# Developer_GT06.net
KiCad netlist of a schematic drawn in Altium Designer
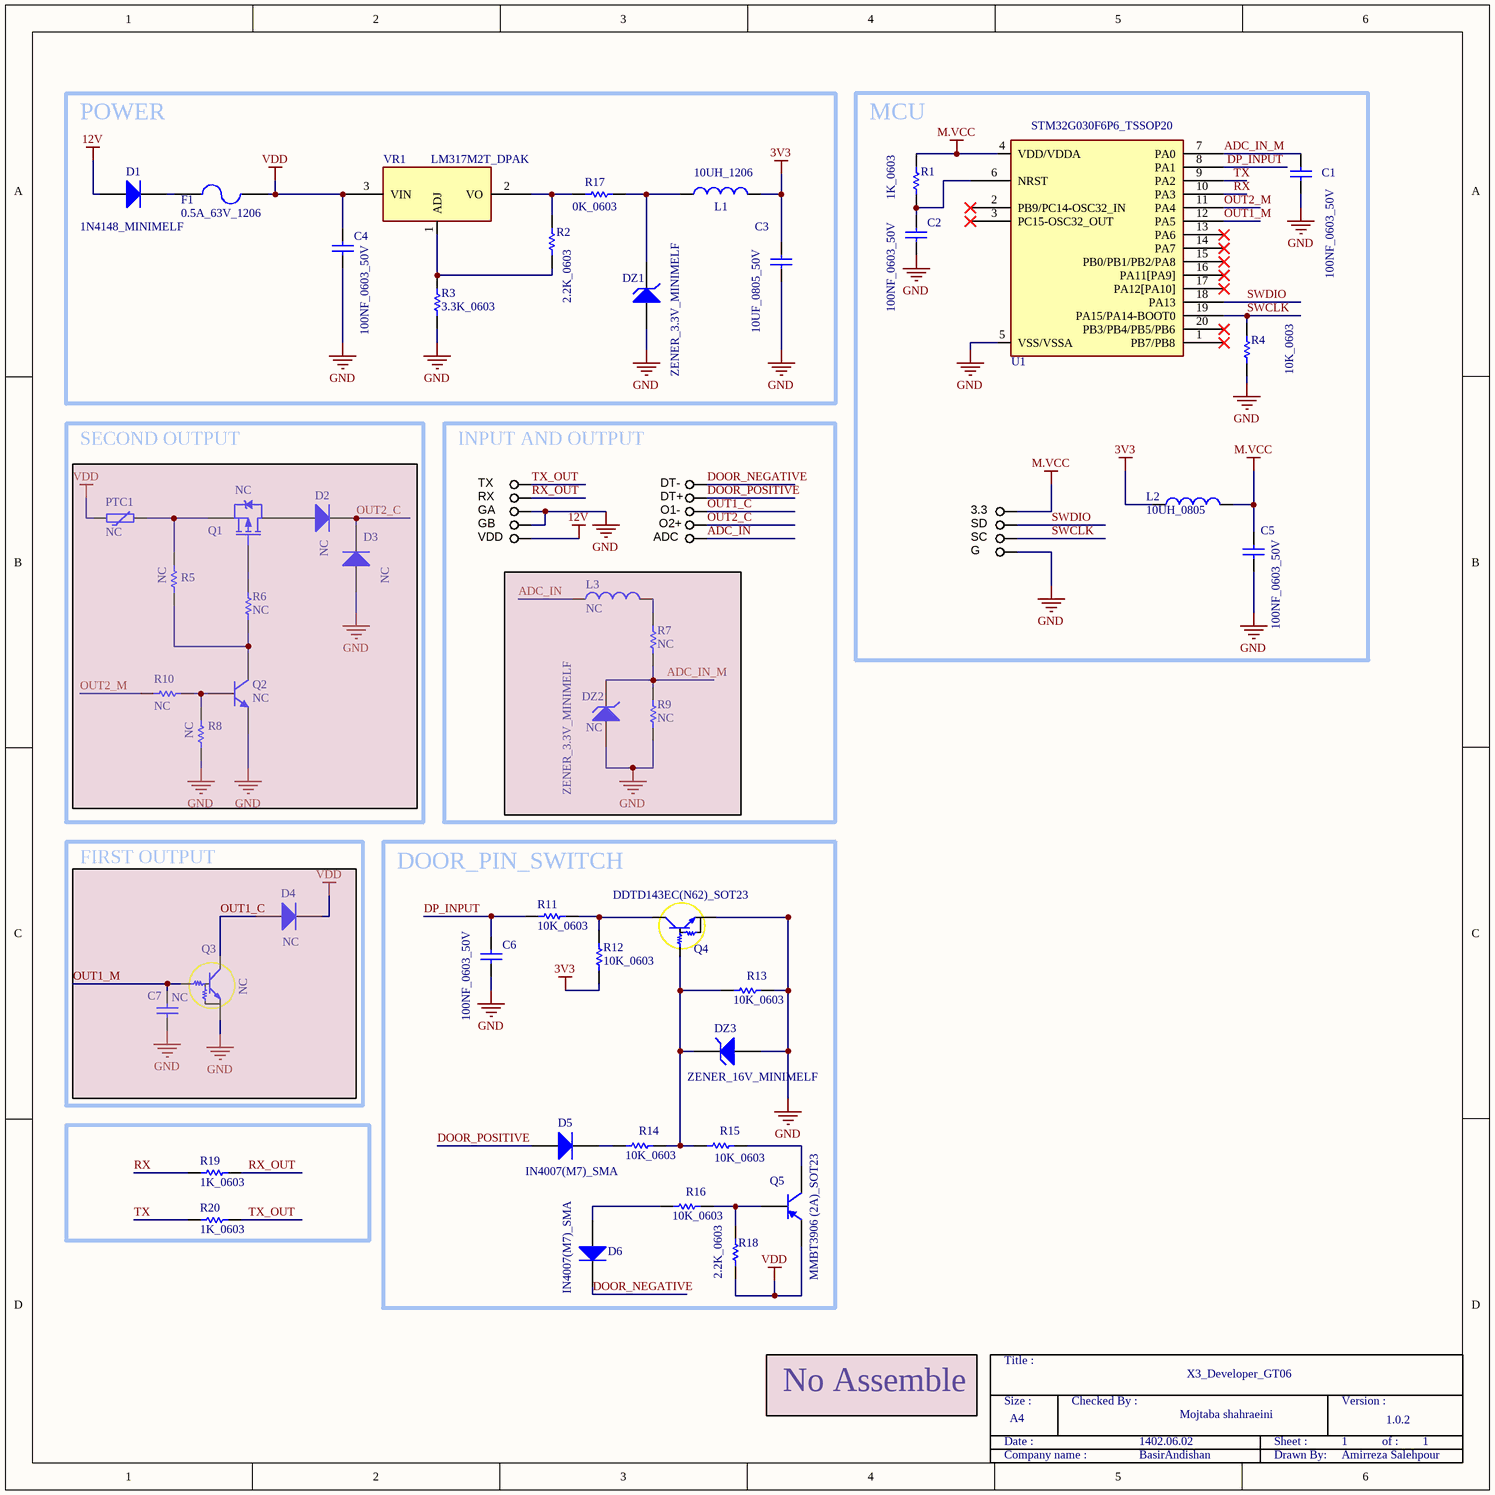
[diagram p0: Developer_GT06.SchDoc]

(export (version "E")
  (design (tool "Eeschema 10.0.6"))
  (components
    (comp (ref "3.3")
      (value "~")
      (footprint "TPSMD_D1")
      (description "TEST POINT")
      (fields (field (name "MANF") "MANF") (field (name "MANF_P#") "MANF_P#"))
      (libsource (lib "GTC Schematic") (part "TESTPOINT_SMD"))
    )
    (comp (ref "ADC")
      (value "~")
      (footprint "TPSMD_D1")
      (description "TEST POINT")
      (fields (field (name "MANF") "MANF") (field (name "MANF_P#") "MANF_P#"))
      (libsource (lib "GTC Schematic") (part "TESTPOINT_SMD"))
    )
    (comp (ref "C1")
      (value "100NF_0603_50V")
      (footprint "Cap_0603_Nominal")
      (libsource (lib "Saeed_New_Lib") (part "Cap"))
    )
    (comp (ref "C2")
      (value "100NF_0603_50V")
      (footprint "Cap_0603_Nominal")
      (libsource (lib "Saeed_New_Lib") (part "Cap"))
    )
    (comp (ref "C3")
      (value "10UF_0805_50V")
      (footprint "Cap_0805_Nominal")
      (libsource (lib "Saeed_New_Lib") (part "Cap"))
    )
    (comp (ref "C4")
      (value "100NF_0603_50V")
      (footprint "Cap_0603_Nominal")
      (libsource (lib "Saeed_New_Lib") (part "Cap"))
    )
    (comp (ref "C5")
      (value "100NF_0603_50V")
      (footprint "Cap_0603_Nominal")
      (libsource (lib "Saeed_New_Lib") (part "Cap"))
    )
    (comp (ref "C6")
      (value "100NF_0603_50V")
      (footprint "Cap_0603_Nominal")
      (libsource (lib "Saeed_New_Lib") (part "Cap"))
    )
    (comp (ref "C7")
      (value "NC")
      (footprint "Cap_0603_Nominal")
      (description "100NF_0603_50V")
      (libsource (lib "Saeed_New_Lib") (part "Cap"))
    )
    (comp (ref "D1")
      (value "1N4148_MINIMELF")
      (footprint "DIODE_SMA")
      (libsource (lib "Amir_Library") (part "Diode"))
    )
    (comp (ref "D2")
      (value "NC")
      (footprint "DIODE_SMA")
      (description "IN4007(M7)_SMA")
      (libsource (lib "My Shematic") (part "Diode"))
    )
    (comp (ref "D3")
      (value "NC")
      (footprint "DIODE_SMA")
      (description "IN4007(M7)_SMA")
      (libsource (lib "My Shematic") (part "Diode"))
    )
    (comp (ref "D4")
      (value "NC")
      (footprint "DIODE_SMA")
      (description "IN4007(M7)_SMA")
      (libsource (lib "My Shematic") (part "Diode"))
    )
    (comp (ref "D5")
      (value "IN4007(M7)_SMA")
      (footprint "DIODE_SMA")
      (libsource (lib "My Shematic") (part "Diode"))
    )
    (comp (ref "D6")
      (value "IN4007(M7)_SMA")
      (footprint "DIODE_SMA")
      (libsource (lib "My Shematic") (part "Diode"))
    )
    (comp (ref "DT+")
      (value "~")
      (footprint "TPSMD_D1")
      (description "TEST POINT")
      (fields (field (name "MANF") "MANF") (field (name "MANF_P#") "MANF_P#"))
      (libsource (lib "GTC Schematic") (part "TESTPOINT_SMD"))
    )
    (comp (ref "DT-")
      (value "~")
      (footprint "TPSMD_D1")
      (description "TEST POINT")
      (fields (field (name "MANF") "MANF") (field (name "MANF_P#") "MANF_P#"))
      (libsource (lib "GTC Schematic") (part "TESTPOINT_SMD"))
    )
    (comp (ref "DZ1")
      (value "ZENER_3.3V_MINIMELF")
      (footprint "Diode_ZENER_MINIMELF")
      (libsource (lib "Amir_Library") (part "Diode_Zener"))
    )
    (comp (ref "DZ2")
      (value "NC")
      (footprint "Diode_ZENER_MINIMELF")
      (fields (field (name "ALTIUM_VALUE") "ZENER_3.3V_MINIMELF"))
      (libsource (lib "Amir_Library") (part "Diode_Zener"))
    )
    (comp (ref "DZ3")
      (value "ZENER_16V_MINIMELF")
      (footprint "Diode_ZENER_MINIMELF")
      (libsource (lib "Amir_Library") (part "Diode_Zener"))
    )
    (comp (ref "F1")
      (value "0.5A_63V_1206")
      (footprint "FUSE_1206_NOMINAL")
      (description "Marking Code:F")
      (libsource (lib "Amir_Library") (part "FUSE"))
    )
    (comp (ref "G")
      (value "~")
      (footprint "TPSMD_D1")
      (description "TEST POINT")
      (fields (field (name "MANF") "MANF") (field (name "MANF_P#") "MANF_P#"))
      (libsource (lib "GTC Schematic") (part "TESTPOINT_SMD"))
    )
    (comp (ref "GA")
      (value "~")
      (footprint "TPSMD_D1")
      (description "TEST POINT")
      (fields (field (name "MANF") "MANF") (field (name "MANF_P#") "MANF_P#"))
      (libsource (lib "GTC Schematic") (part "TESTPOINT_SMD"))
    )
    (comp (ref "GB")
      (value "~")
      (footprint "TPSMD_D1")
      (description "TEST POINT")
      (fields (field (name "MANF") "MANF") (field (name "MANF_P#") "MANF_P#"))
      (libsource (lib "GTC Schematic") (part "TESTPOINT_SMD"))
    )
    (comp (ref "L1")
      (value "10UH_1206")
      (footprint "INDUCTOR_1206_NOMINAL")
      (libsource (lib "Saeed_New_Lib") (part "Inductor"))
    )
    (comp (ref "L2")
      (value "10UH_0805")
      (footprint "INDUCTOR_0805_Nominal")
      (libsource (lib "Saeed_New_Lib") (part "Inductor"))
    )
    (comp (ref "L3")
      (value "NC")
      (footprint "INDUCTOR_0805_Nominal")
      (description "10UH_0805")
      (libsource (lib "GTC Shem") (part "Inductor"))
    )
    (comp (ref "O1-")
      (value "~")
      (footprint "TPSMD_D1")
      (description "TEST POINT")
      (fields (field (name "MANF") "MANF") (field (name "MANF_P#") "MANF_P#"))
      (libsource (lib "GTC Schematic") (part "TESTPOINT_SMD"))
    )
    (comp (ref "O2+")
      (value "~")
      (footprint "TPSMD_D1")
      (description "TEST POINT")
      (fields (field (name "MANF") "MANF") (field (name "MANF_P#") "MANF_P#"))
      (libsource (lib "GTC Schematic") (part "TESTPOINT_SMD"))
    )
    (comp (ref "PTC1")
      (value "NC")
      (footprint "PTC_1812")
      (description "TLC-MSMD050(Marking Code: T050)")
      (libsource (lib "GTC Schematic") (part "PTC"))
    )
    (comp (ref "Q1")
      (value "NC")
      (footprint "SOT23_MOSFET")
      (description "SI2309A(MS29)_SOT23")
      (fields (field (name "PUBLISHER") "Altium Limited"))
      (libsource (lib "GTC Schematic") (part "MOSFET-P"))
    )
    (comp (ref "Q2")
      (value "NC")
      (footprint "SOT23_BJT")
      (description "MMBT3904")
      (libsource (lib "GTC Schematic") (part "MMBT3904"))
    )
    (comp (ref "Q3")
      (value "NC")
      (footprint "SOT23")
      (description "DDTD143EC(N62)_SOT23")
      (libsource (lib "My Shematic") (part "NPN_Digital"))
    )
    (comp (ref "Q4")
      (value "DDTD143EC(N62)_SOT23")
      (footprint "SOT23")
      (libsource (lib "") (part "NPN_Digital_1"))
    )
    (comp (ref "Q5")
      (value "MMBT3906 (2A)_SOT23")
      (footprint "SOT23_BJT")
      (libsource (lib "GTC Shem") (part "MMBT3906"))
    )
    (comp (ref "R1")
      (value "1K_0603")
      (footprint "Res_0603_Nominal")
      (libsource (lib "Amir_Library") (part "RES"))
    )
    (comp (ref "R2")
      (value "2.2K_0603")
      (footprint "Res_0603_Nominal")
      (libsource (lib "Amir_Library") (part "RES"))
    )
    (comp (ref "R3")
      (value "3.3K_0603")
      (footprint "Res_0603_Nominal")
      (libsource (lib "Amir_Library") (part "RES"))
    )
    (comp (ref "R4")
      (value "10K_0603")
      (footprint "Res_0603_Nominal")
      (libsource (lib "Amir_Library") (part "RES"))
    )
    (comp (ref "R5")
      (value "NC")
      (footprint "Res_0603_Nominal")
      (description "10K_0603")
      (libsource (lib "Amir_Library") (part "RES"))
    )
    (comp (ref "R6")
      (value "NC")
      (footprint "Res_0603_Nominal")
      (description "10K_0603")
      (libsource (lib "Amir_Library") (part "RES"))
    )
    (comp (ref "R7")
      (value "NC")
      (footprint "Res_0603_Nominal")
      (description "22K_0603")
      (libsource (lib "Amir_Library") (part "RES"))
    )
    (comp (ref "R8")
      (value "NC")
      (footprint "Res_0603_Nominal")
      (description "10K_0603")
      (libsource (lib "Amir_Library") (part "RES"))
    )
    (comp (ref "R9")
      (value "NC")
      (footprint "Res_0603_Nominal")
      (description "2.2K_0603")
      (libsource (lib "Amir_Library") (part "RES"))
    )
    (comp (ref "R10")
      (value "NC")
      (footprint "Res_0603_Nominal")
      (description "10K_0603")
      (libsource (lib "Amir_Library") (part "RES"))
    )
    (comp (ref "R11")
      (value "10K_0603")
      (footprint "Res_0603_Nominal")
      (libsource (lib "Amir_Library") (part "RES"))
    )
    (comp (ref "R12")
      (value "10K_0603")
      (footprint "Res_0603_Nominal")
      (libsource (lib "Amir_Library") (part "RES"))
    )
    (comp (ref "R13")
      (value "10K_0603")
      (footprint "Res_0603_Nominal")
      (libsource (lib "Amir_Library") (part "RES"))
    )
    (comp (ref "R14")
      (value "10K_0603")
      (footprint "Res_0603_Nominal")
      (libsource (lib "Amir_Library") (part "RES"))
    )
    (comp (ref "R15")
      (value "10K_0603")
      (footprint "Res_0603_Nominal")
      (libsource (lib "Amir_Library") (part "RES"))
    )
    (comp (ref "R16")
      (value "10K_0603")
      (footprint "Res_0603_Nominal")
      (libsource (lib "Amir_Library") (part "RES"))
    )
    (comp (ref "R17")
      (value "0K_0603")
      (footprint "Res_0603_Nominal")
      (libsource (lib "Amir_Library") (part "RES"))
    )
    (comp (ref "R18")
      (value "2.2K_0603")
      (footprint "Res_0603_Nominal")
      (libsource (lib "Amir_Library") (part "RES"))
    )
    (comp (ref "R19")
      (value "1K_0603")
      (footprint "Res_0603_Nominal")
      (libsource (lib "Amir_Library") (part "RES"))
    )
    (comp (ref "R20")
      (value "1K_0603")
      (footprint "Res_0603_Nominal")
      (libsource (lib "Amir_Library") (part "RES"))
    )
    (comp (ref "RX")
      (value "~")
      (footprint "TPSMD_D1")
      (description "TEST POINT")
      (fields (field (name "MANF") "MANF") (field (name "MANF_P#") "MANF_P#"))
      (libsource (lib "GTC Schematic") (part "TESTPOINT_SMD"))
    )
    (comp (ref "SC")
      (value "~")
      (footprint "TPSMD_D1")
      (description "TEST POINT")
      (fields (field (name "MANF") "MANF") (field (name "MANF_P#") "MANF_P#"))
      (libsource (lib "GTC Schematic") (part "TESTPOINT_SMD"))
    )
    (comp (ref "SD")
      (value "~")
      (footprint "TPSMD_D1")
      (description "TEST POINT")
      (fields (field (name "MANF") "MANF") (field (name "MANF_P#") "MANF_P#"))
      (libsource (lib "GTC Schematic") (part "TESTPOINT_SMD"))
    )
    (comp (ref "TX")
      (value "~")
      (footprint "TPSMD_D1")
      (description "TEST POINT")
      (fields (field (name "MANF") "MANF") (field (name "MANF_P#") "MANF_P#"))
      (libsource (lib "GTC Schematic") (part "TESTPOINT_SMD"))
    )
    (comp (ref "U1")
      (value "STM32G030F6P6_TSSOP20")
      (footprint "SOG65_20")
      (description "MCU, STM32 ARM 32-bit, Cortex M0, 64KB FLASH, 8KB SRAM")
      (fields (field (name "MANF") "ST") (field (name "MANF_P#") "STM32F103C8T6"))
      (libsource (lib "GTC Schematic") (part "STM32G030x6"))
    )
    (comp (ref "VDD")
      (value "~")
      (footprint "TPSMD_D1")
      (description "TEST POINT")
      (fields (field (name "MANF") "MANF") (field (name "MANF_P#") "MANF_P#"))
      (libsource (lib "GTC Schematic") (part "TESTPOINT_SMD"))
    )
    (comp (ref "VR1")
      (value "LM317M2T_DPAK")
      (footprint "DPAK")
      (description "REG, Linear, Adjustable, 1.5A, TO-220")
      (fields
        (field (name "MANF_P#") "LM317KC, LM317T, LM317HVT, LM317BTG")
        (field (name "MANF") "TI, ST, ON")
      )
      (libsource (lib "GTC Schematic") (part "VREG_LM317_TO220"))
    )
  )
  (nets
    (net (code "1") (name "/ADC_IN") (class "Default")
      (node (ref "ADC") (pin "1") (pinfunction "1_1") (pintype "passive"))
      (node (ref "L3") (pin "1") (pinfunction "1_1") (pintype "passive"))
    )
    (net (code "2") (name "/ADC_IN_M") (class "Default")
      (node (ref "C1") (pin "2") (pinfunction "2_2") (pintype "passive"))
      (node (ref "DZ2") (pin "2") (pinfunction "K_2") (pintype "passive"))
      (node (ref "R7") (pin "2") (pinfunction "2_2") (pintype "passive"))
      (node (ref "R9") (pin "1") (pinfunction "1_1") (pintype "passive"))
      (node (ref "U1") (pin "7") (pinfunction "PA0_7") (pintype "passive"))
    )
    (net (code "3") (name "/DOOR_NEGATIVE") (class "Default")
      (node (ref "D6") (pin "2") (pinfunction "K_2") (pintype "passive"))
      (node (ref "DT-") (pin "1") (pinfunction "1_1") (pintype "passive"))
    )
    (net (code "4") (name "/DOOR_POSITIVE") (class "Default")
      (node (ref "D5") (pin "1") (pinfunction "A_1") (pintype "passive"))
      (node (ref "DT+") (pin "1") (pinfunction "1_1") (pintype "passive"))
    )
    (net (code "5") (name "/DP_INPUT") (class "Default")
      (node (ref "C6") (pin "2") (pinfunction "2_2") (pintype "passive"))
      (node (ref "R11") (pin "1") (pinfunction "1_1") (pintype "passive"))
      (node (ref "U1") (pin "8") (pinfunction "PA1_8") (pintype "passive"))
    )
    (net (code "6") (name "/OUT1_C") (class "Default")
      (node (ref "D4") (pin "1") (pinfunction "A_1") (pintype "passive"))
      (node (ref "O1-") (pin "1") (pinfunction "1_1") (pintype "passive"))
      (node (ref "Q3") (pin "3") (pinfunction "C_3") (pintype "passive"))
    )
    (net (code "7") (name "/OUT1_M") (class "Default")
      (node (ref "C7") (pin "2") (pinfunction "2_2") (pintype "passive"))
      (node (ref "Q3") (pin "1") (pinfunction "B_1") (pintype "passive"))
      (node (ref "U1") (pin "12") (pinfunction "PA5_12") (pintype "passive"))
    )
    (net (code "8") (name "/OUT2_C") (class "Default")
      (node (ref "D2") (pin "2") (pinfunction "K_2") (pintype "passive"))
      (node (ref "D3") (pin "2") (pinfunction "K_2") (pintype "passive"))
      (node (ref "O2+") (pin "1") (pinfunction "1_1") (pintype "passive"))
    )
    (net (code "9") (name "/OUT2_M") (class "Default")
      (node (ref "R10") (pin "2") (pinfunction "2_2") (pintype "passive"))
      (node (ref "U1") (pin "11") (pinfunction "PA4_11") (pintype "passive"))
    )
    (net (code "10") (name "/RX") (class "Default")
      (node (ref "R19") (pin "1") (pinfunction "1_1") (pintype "passive"))
      (node (ref "U1") (pin "10") (pinfunction "PA3_10") (pintype "passive"))
    )
    (net (code "11") (name "/RX_OUT") (class "Default")
      (node (ref "R19") (pin "2") (pinfunction "2_2") (pintype "passive"))
      (node (ref "RX") (pin "1") (pinfunction "1_1") (pintype "passive"))
    )
    (net (code "12") (name "/SWCLK") (class "Default")
      (node (ref "R4") (pin "1") (pinfunction "1_1") (pintype "passive"))
      (node (ref "SC") (pin "1") (pinfunction "1_1") (pintype "passive"))
      (node (ref "U1") (pin "19") (pinfunction "PA15/PA14-BOOT0_19") (pintype "passive"))
    )
    (net (code "13") (name "/SWDIO") (class "Default")
      (node (ref "SD") (pin "1") (pinfunction "1_1") (pintype "passive"))
      (node (ref "U1") (pin "18") (pinfunction "PA13_18") (pintype "passive"))
    )
    (net (code "14") (name "/TX") (class "Default")
      (node (ref "R20") (pin "1") (pinfunction "1_1") (pintype "passive"))
      (node (ref "U1") (pin "9") (pinfunction "PA2_9") (pintype "passive"))
    )
    (net (code "15") (name "/TX_OUT") (class "Default")
      (node (ref "R20") (pin "2") (pinfunction "2_2") (pintype "passive"))
      (node (ref "TX") (pin "1") (pinfunction "1_1") (pintype "passive"))
    )
    (net (code "16") (name "3V3") (class "Default")
      (node (ref "C3") (pin "2") (pinfunction "2_2") (pintype "passive"))
      (node (ref "L1") (pin "2") (pinfunction "2_2") (pintype "passive"))
      (node (ref "L2") (pin "1") (pinfunction "1_1") (pintype "passive"))
      (node (ref "R12") (pin "2") (pinfunction "2_2") (pintype "passive"))
    )
    (net (code "17") (name "12V") (class "Default")
      (node (ref "D1") (pin "1") (pinfunction "A_1") (pintype "passive"))
      (node (ref "VDD") (pin "1") (pinfunction "1_1") (pintype "passive"))
    )
    (net (code "18") (name "GND") (class "Default")
      (node (ref "C1") (pin "1") (pinfunction "1_1") (pintype "passive"))
      (node (ref "C2") (pin "1") (pinfunction "1_1") (pintype "passive"))
      (node (ref "C3") (pin "1") (pinfunction "1_1") (pintype "passive"))
      (node (ref "C4") (pin "1") (pinfunction "1_1") (pintype "passive"))
      (node (ref "C5") (pin "1") (pinfunction "1_1") (pintype "passive"))
      (node (ref "C6") (pin "1") (pinfunction "1_1") (pintype "passive"))
      (node (ref "C7") (pin "1") (pinfunction "1_1") (pintype "passive"))
      (node (ref "D3") (pin "1") (pinfunction "A_1") (pintype "passive"))
      (node (ref "DZ1") (pin "1") (pinfunction "A_1") (pintype "passive"))
      (node (ref "DZ2") (pin "1") (pinfunction "A_1") (pintype "passive"))
      (node (ref "DZ3") (pin "1") (pinfunction "A_1") (pintype "passive"))
      (node (ref "G") (pin "1") (pinfunction "1_1") (pintype "passive"))
      (node (ref "GA") (pin "1") (pinfunction "1_1") (pintype "passive"))
      (node (ref "GB") (pin "1") (pinfunction "1_1") (pintype "passive"))
      (node (ref "Q2") (pin "2") (pinfunction "E_2") (pintype "passive"))
      (node (ref "Q3") (pin "2") (pinfunction "E_2") (pintype "passive"))
      (node (ref "Q4") (pin "2") (pinfunction "E_2") (pintype "passive"))
      (node (ref "R13") (pin "1") (pinfunction "1_1") (pintype "passive"))
      (node (ref "R3") (pin "2") (pinfunction "2_2") (pintype "passive"))
      (node (ref "R4") (pin "2") (pinfunction "2_2") (pintype "passive"))
      (node (ref "R8") (pin "2") (pinfunction "2_2") (pintype "passive"))
      (node (ref "R9") (pin "2") (pinfunction "2_2") (pintype "passive"))
      (node (ref "U1") (pin "5") (pinfunction "VSS/VSSA_5") (pintype "passive"))
    )
    (net (code "19") (name "M.VCC") (class "Default")
      (node (ref "3.3") (pin "1") (pinfunction "1_1") (pintype "passive"))
      (node (ref "C5") (pin "2") (pinfunction "2_2") (pintype "passive"))
      (node (ref "L2") (pin "2") (pinfunction "2_2") (pintype "passive"))
      (node (ref "R1") (pin "1") (pinfunction "1_1") (pintype "passive"))
      (node (ref "U1") (pin "4") (pinfunction "VDD/VDDA_4") (pintype "passive"))
    )
    (net (code "20") (name "Net-(D1-K)") (class "Default")
      (node (ref "D1") (pin "2") (pinfunction "K_2") (pintype "passive"))
      (node (ref "F1") (pin "1") (pinfunction "1_1") (pintype "passive"))
    )
    (net (code "21") (name "Net-(D2-A)") (class "Default")
      (node (ref "D2") (pin "1") (pinfunction "A_1") (pintype "passive"))
      (node (ref "Q1") (pin "3") (pinfunction "D_3") (pintype "passive"))
    )
    (net (code "22") (name "Net-(D5-K)") (class "Default")
      (node (ref "D5") (pin "2") (pinfunction "K_2") (pintype "passive"))
      (node (ref "R14") (pin "2") (pinfunction "2_2") (pintype "passive"))
    )
    (net (code "23") (name "Net-(D6-A)") (class "Default")
      (node (ref "D6") (pin "1") (pinfunction "A_1") (pintype "passive"))
      (node (ref "R16") (pin "2") (pinfunction "2_2") (pintype "passive"))
    )
    (net (code "24") (name "Net-(DZ1-K)") (class "Default")
      (node (ref "DZ1") (pin "2") (pinfunction "K_2") (pintype "passive"))
      (node (ref "L1") (pin "1") (pinfunction "1_1") (pintype "passive"))
      (node (ref "R17") (pin "2") (pinfunction "2_2") (pintype "passive"))
    )
    (net (code "25") (name "Net-(DZ3-K)") (class "Default")
      (node (ref "DZ3") (pin "2") (pinfunction "K_2") (pintype "passive"))
      (node (ref "Q4") (pin "1") (pinfunction "B_1") (pintype "passive"))
      (node (ref "R13") (pin "2") (pinfunction "2_2") (pintype "passive"))
      (node (ref "R14") (pin "1") (pinfunction "1_1") (pintype "passive"))
      (node (ref "R15") (pin "2") (pinfunction "2_2") (pintype "passive"))
    )
    (net (code "26") (name "Net-(L3-Pad2)") (class "Default")
      (node (ref "L3") (pin "2") (pinfunction "2_2") (pintype "passive"))
      (node (ref "R7") (pin "1") (pinfunction "1_1") (pintype "passive"))
    )
    (net (code "27") (name "Net-(Q1-G)") (class "Default")
      (node (ref "Q1") (pin "1") (pinfunction "G_1") (pintype "passive"))
      (node (ref "R6") (pin "1") (pinfunction "1_1") (pintype "passive"))
    )
    (net (code "28") (name "Net-(Q1-S)") (class "Default")
      (node (ref "PTC1") (pin "2") (pinfunction "2_2") (pintype "passive"))
      (node (ref "Q1") (pin "2") (pinfunction "S_2") (pintype "passive"))
      (node (ref "R5") (pin "1") (pinfunction "1_1") (pintype "passive"))
    )
    (net (code "29") (name "Net-(Q2-B)") (class "Default")
      (node (ref "Q2") (pin "1") (pinfunction "B_1") (pintype "passive"))
      (node (ref "R10") (pin "1") (pinfunction "1_1") (pintype "passive"))
      (node (ref "R8") (pin "1") (pinfunction "1_1") (pintype "passive"))
    )
    (net (code "30") (name "Net-(Q2-C)") (class "Default")
      (node (ref "Q2") (pin "3") (pinfunction "C_3") (pintype "passive"))
      (node (ref "R5") (pin "2") (pinfunction "2_2") (pintype "passive"))
      (node (ref "R6") (pin "2") (pinfunction "2_2") (pintype "passive"))
    )
    (net (code "31") (name "Net-(Q4-C)") (class "Default")
      (node (ref "Q4") (pin "3") (pinfunction "C_3") (pintype "passive"))
      (node (ref "R11") (pin "2") (pinfunction "2_2") (pintype "passive"))
      (node (ref "R12") (pin "1") (pinfunction "1_1") (pintype "passive"))
    )
    (net (code "32") (name "Net-(Q5-B)") (class "Default")
      (node (ref "Q5") (pin "1") (pinfunction "B_1") (pintype "passive"))
      (node (ref "R16") (pin "1") (pinfunction "1_1") (pintype "passive"))
      (node (ref "R18") (pin "2") (pinfunction "2_2") (pintype "passive"))
    )
    (net (code "33") (name "Net-(Q5-C)") (class "Default")
      (node (ref "Q5") (pin "3") (pinfunction "C_3") (pintype "passive"))
      (node (ref "R15") (pin "1") (pinfunction "1_1") (pintype "passive"))
    )
    (net (code "34") (name "Net-(U1-NRST)") (class "Default")
      (node (ref "C2") (pin "2") (pinfunction "2_2") (pintype "passive"))
      (node (ref "R1") (pin "2") (pinfunction "2_2") (pintype "passive"))
      (node (ref "U1") (pin "6") (pinfunction "NRST_6") (pintype "passive"))
    )
    (net (code "35") (name "Net-(VR1-ADJ)") (class "Default")
      (node (ref "R2") (pin "2") (pinfunction "2_2") (pintype "passive"))
      (node (ref "R3") (pin "1") (pinfunction "1_1") (pintype "passive"))
      (node (ref "VR1") (pin "1") (pinfunction "ADJ_1") (pintype "passive"))
    )
    (net (code "36") (name "Net-(VR1-VO)") (class "Default")
      (node (ref "R17") (pin "1") (pinfunction "1_1") (pintype "passive"))
      (node (ref "R2") (pin "1") (pinfunction "1_1") (pintype "passive"))
      (node (ref "VR1") (pin "2") (pinfunction "VO_2") (pintype "passive"))
    )
    (net (code "37") (name "VDD") (class "Default")
      (node (ref "C4") (pin "2") (pinfunction "2_2") (pintype "passive"))
      (node (ref "D4") (pin "2") (pinfunction "K_2") (pintype "passive"))
      (node (ref "F1") (pin "2") (pinfunction "2_2") (pintype "passive"))
      (node (ref "PTC1") (pin "1") (pinfunction "1_1") (pintype "passive"))
      (node (ref "Q5") (pin "2") (pinfunction "E_2") (pintype "passive"))
      (node (ref "R18") (pin "1") (pinfunction "1_1") (pintype "passive"))
      (node (ref "VR1") (pin "3") (pinfunction "VIN_3") (pintype "passive"))
    )
    (net (code "38") (name "unconnected-(U1-PA6-Pad13)") (class "Default")
      (node (ref "U1") (pin "13") (pinfunction "PA6_13") (pintype "passive+no_connect"))
    )
    (net (code "39") (name "unconnected-(U1-PA7-Pad14)") (class "Default")
      (node (ref "U1") (pin "14") (pinfunction "PA7_14") (pintype "passive+no_connect"))
    )
    (net (code "40") (name "unconnected-(U1-PA11[PA9]-Pad16)") (class "Default")
      (node (ref "U1") (pin "16") (pinfunction "PA11[PA9]_16") (pintype "passive+no_connect"))
    )
    (net (code "41") (name "unconnected-(U1-PA12[PA10]-Pad17)") (class "Default")
      (node (ref "U1") (pin "17") (pinfunction "PA12[PA10]_17") (pintype "passive+no_connect"))
    )
    (net (code "42") (name "unconnected-(U1-PB0{slash}PB1{slash}PB2{slash}PA8-Pad15)") (class "Default")
      (node (ref "U1") (pin "15") (pinfunction "PB0/PB1/PB2/PA8_15") (pintype "passive+no_connect"))
    )
    (net (code "43") (name "unconnected-(U1-PB3{slash}PB4{slash}PB5{slash}PB6-Pad20)") (class "Default")
      (node (ref "U1") (pin "20") (pinfunction "PB3/PB4/PB5/PB6_20") (pintype "passive+no_connect"))
    )
    (net (code "44") (name "unconnected-(U1-PB7{slash}PB8-Pad1)") (class "Default")
      (node (ref "U1") (pin "1") (pinfunction "PB7/PB8_1") (pintype "passive+no_connect"))
    )
    (net (code "45") (name "unconnected-(U1-PB9{slash}PC14-OSC32_IN-Pad2)") (class "Default")
      (node (ref "U1") (pin "2") (pinfunction "PB9/PC14-OSC32_IN_2") (pintype "passive+no_connect"))
    )
    (net (code "46") (name "unconnected-(U1-PC15-OSC32_OUT-Pad3)") (class "Default")
      (node (ref "U1") (pin "3") (pinfunction "PC15-OSC32_OUT_3") (pintype "passive+no_connect"))
    )
  )
)
